# Piirikaavio.net
KiCad netlist of a schematic drawn in Altium Designer
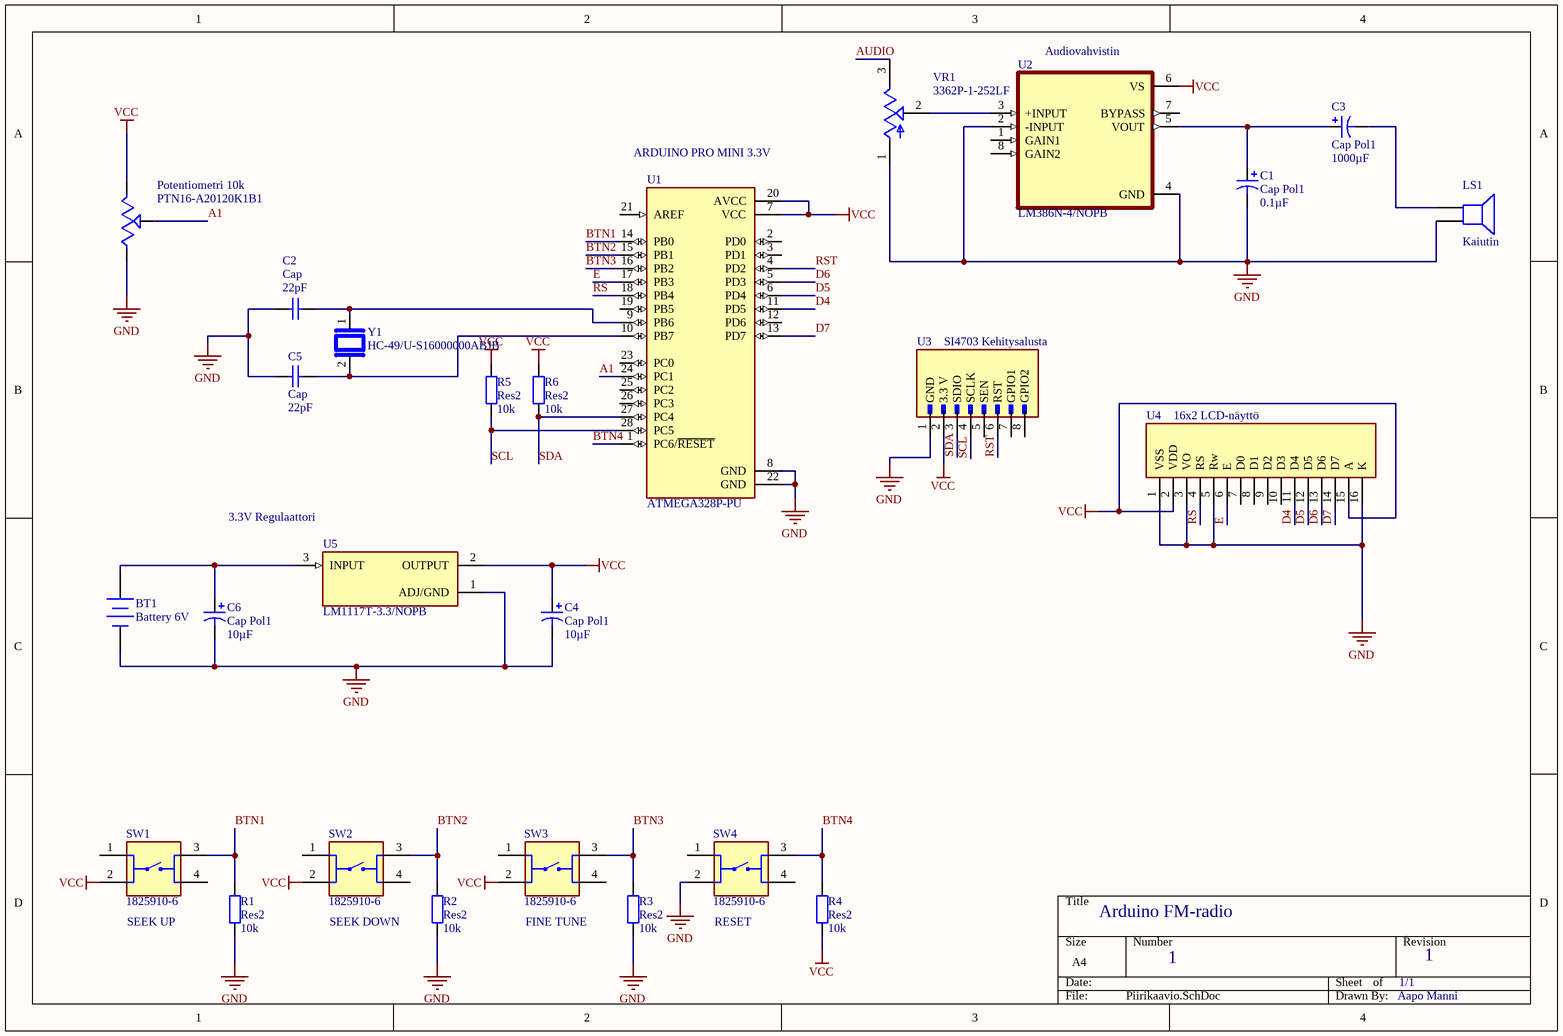
[diagram p0: Piirikaavio.SchDoc]

(export (version "E")
  (design (tool "Eeschema 10.0.6"))
  (components
    (comp (ref "BT1")
      (value "Battery 6V")
      (footprint "BAT-2")
      (description "Multicell Battery")
      (fields (field (name "PUBLISHER") "Altium Limited"))
      (libsource (lib "Miscellaneous Devices") (part "Battery"))
    )
    (comp (ref "C1")
      (value "Cap Pol1")
      (footprint "RB7.6-15")
      (description "Polarized Capacitor (Radial)")
      (fields (field (name "ALTIUM_VALUE") "0.1µF") (field (name "PUBLISHER") "Altium Limited"))
      (libsource (lib "Miscellaneous Devices") (part "Cap Pol1"))
    )
    (comp (ref "C2")
      (value "Cap")
      (footprint "RAD-0.3")
      (description "Capacitor")
      (fields (field (name "ALTIUM_VALUE") "22pF") (field (name "PUBLISHER") "Altium Limited"))
      (libsource (lib "Miscellaneous Devices") (part "Cap"))
    )
    (comp (ref "C3")
      (value "Cap Pol1")
      (footprint "RB7.6-15")
      (description "Polarized Capacitor (Radial)")
      (fields (field (name "ALTIUM_VALUE") "1000µF") (field (name "PUBLISHER") "Altium Limited"))
      (libsource (lib "Miscellaneous Devices") (part "Cap Pol1"))
    )
    (comp (ref "C4")
      (value "Cap Pol1")
      (footprint "RB7.6-15")
      (description "Polarized Capacitor (Radial)")
      (fields (field (name "ALTIUM_VALUE") "10µF") (field (name "PUBLISHER") "Altium Limited"))
      (libsource (lib "Miscellaneous Devices") (part "Cap Pol1"))
    )
    (comp (ref "C5")
      (value "Cap")
      (footprint "RAD-0.3")
      (description "Capacitor")
      (fields (field (name "ALTIUM_VALUE") "22pF") (field (name "PUBLISHER") "Altium Limited"))
      (libsource (lib "Miscellaneous Devices") (part "Cap"))
    )
    (comp (ref "C6")
      (value "Cap Pol1")
      (footprint "RB7.6-15")
      (description "Polarized Capacitor (Radial)")
      (fields (field (name "ALTIUM_VALUE") "10µF") (field (name "PUBLISHER") "Altium Limited"))
      (libsource (lib "Miscellaneous Devices") (part "Cap Pol1"))
    )
    (comp (ref "LS1")
      (value "Kaiutin")
      (footprint "PIN2")
      (description "Loudspeaker")
      (fields (field (name "PUBLISHER") "Altium Limited"))
      (libsource (lib "Miscellaneous Devices") (part "Speaker"))
    )
    (comp (ref "Potentiometri 10k")
      (value "PTN16-A20120K1B1")
      (footprint "POT_PTN16-A20120K1B1")
      (fields (field (name "MF") "CUI Devices"))
      (libsource (lib "PTN16-A20120K1B1") (part "PTN16-A20120K1B1"))
    )
    (comp (ref "R1")
      (value "Res2")
      (footprint "AXIAL-0.4")
      (description "Resistor 10k")
      (fields (field (name "ALTIUM_VALUE") "10k") (field (name "PUBLISHER") "Altium Limited"))
      (libsource (lib "Miscellaneous Devices") (part "Res2"))
    )
    (comp (ref "R2")
      (value "Res2")
      (footprint "AXIAL-0.4")
      (description "Resistor 10k")
      (fields (field (name "ALTIUM_VALUE") "10k") (field (name "PUBLISHER") "Altium Limited"))
      (libsource (lib "Miscellaneous Devices") (part "Res2"))
    )
    (comp (ref "R3")
      (value "Res2")
      (footprint "AXIAL-0.4")
      (description "Resistor 10k")
      (fields (field (name "ALTIUM_VALUE") "10k") (field (name "PUBLISHER") "Altium Limited"))
      (libsource (lib "Miscellaneous Devices") (part "Res2"))
    )
    (comp (ref "R4")
      (value "Res2")
      (footprint "AXIAL-0.4")
      (description "Resistor 10k")
      (fields (field (name "ALTIUM_VALUE") "10k") (field (name "PUBLISHER") "Altium Limited"))
      (libsource (lib "Miscellaneous Devices") (part "Res2"))
    )
    (comp (ref "R5")
      (value "Res2")
      (footprint "AXIAL-0.4")
      (description "Resistor 10k")
      (fields (field (name "ALTIUM_VALUE") "10k") (field (name "PUBLISHER") "Altium Limited"))
      (libsource (lib "Miscellaneous Devices") (part "Res2"))
    )
    (comp (ref "R6")
      (value "Res2")
      (footprint "AXIAL-0.4")
      (description "Resistor 10k")
      (fields (field (name "ALTIUM_VALUE") "10k") (field (name "PUBLISHER") "Altium Limited"))
      (libsource (lib "Miscellaneous Devices") (part "Res2"))
    )
    (comp (ref "SW1")
      (value "1825910-6")
      (footprint "SW_1825910-6-4")
      (description "Switch Push Button OFF (ON) SPST Round Button 0.05A 24VDC Momentary Contact PC Pins Thru-Hole")
      (fields (field (name "MF") "TE Connectivity") (field (name "DIGI-KEY_PART_NUMBER") "450-1650-ND"))
      (libsource (lib "1825910-6") (part "1825910-6"))
    )
    (comp (ref "SW2")
      (value "1825910-6")
      (footprint "SW_1825910-6-4")
      (description "Switch Push Button OFF (ON) SPST Round Button 0.05A 24VDC Momentary Contact PC Pins Thru-Hole")
      (fields (field (name "MF") "TE Connectivity") (field (name "DIGI-KEY_PART_NUMBER") "450-1650-ND"))
      (libsource (lib "1825910-6") (part "1825910-6"))
    )
    (comp (ref "SW3")
      (value "1825910-6")
      (footprint "SW_1825910-6-4")
      (description "Switch Push Button OFF (ON) SPST Round Button 0.05A 24VDC Momentary Contact PC Pins Thru-Hole")
      (fields (field (name "MF") "TE Connectivity") (field (name "DIGI-KEY_PART_NUMBER") "450-1650-ND"))
      (libsource (lib "1825910-6") (part "1825910-6"))
    )
    (comp (ref "SW4")
      (value "1825910-6")
      (footprint "SW_1825910-6-4")
      (description "Switch Push Button OFF (ON) SPST Round Button 0.05A 24VDC Momentary Contact PC Pins Thru-Hole")
      (fields (field (name "MF") "TE Connectivity") (field (name "DIGI-KEY_PART_NUMBER") "450-1650-ND"))
      (libsource (lib "1825910-6") (part "1825910-6"))
    )
    (comp (ref "U1")
      (value "ATMEGA328P-PU")
      (footprint "DIP794W46P254L2967H457Q28B")
      (description "ATmega Series 20 MHz 32 KB Flash 2 KB SRAM 8-Bit Microcontroller - DIP-28")
      (libsource (lib "ATMEGA328P-PU") (part "ATMEGA328P-PU"))
    )
    (comp (ref "U2")
      (value "LM386N-4/NOPB")
      (footprint "DIP794W45P254L959H508Q8")
      (description "LM386 Low Voltage Audio Power Amplifier")
      (libsource (lib "LM386N-4_NOPB") (part "LM386N-4/NOPB"))
    )
    (comp (ref "U3")
      (value "SI4703 Kehitysalusta")
      (footprint "HARWIN_M20-9730846")
      (description "Si4703 Evaluation board")
      (fields (field (name "MF") "Harwin") (field (name "MP") "M20-9730846"))
      (libsource (lib "M20-9730846") (part "M20-9730846"))
    )
    (comp (ref "U4")
      (value "16x2 LCD-näyttö")
      (footprint "TE_6-146276-6")
      (description "16x2 Character LCD Module")
      (fields (field (name "MF") "TE Connectivity") (field (name "MP") "6-146276-6"))
      (libsource (lib "6-146276-6") (part "6-146276-6"))
    )
    (comp (ref "U5")
      (value "LM1117T-3.3/NOPB")
      (footprint "TO254P1054X470X1955-3")
      (description "800-mA 15-V linear voltage regulator")
      (fields (field (name "MF") "Texas Instruments"))
      (libsource (lib "LM1117T-3.3_NOPB") (part "LM1117T-3.3/NOPB"))
    )
    (comp (ref "VR1")
      (value "3362P-1-252LF")
      (footprint "TRIM_3362P-1-252LF")
      (description "10 kOhms Pins Through Hole Trimmer Potentiometer Cermet 1 Turn Top Adjustment")
      (fields (field (name "MF") "Bourns"))
      (libsource (lib "3362P-1-252LF") (part "3362P-1-252LF"))
    )
    (comp (ref "Y1")
      (value "HC-49/U-S16000000ABJB")
      (footprint "XTAL_HC49P488W43L1150T466H350")
      (description "8 MHz Crystal  / HC-49/US")
      (fields (field (name "MF") "Citizen Finedevice"))
      (libsource (lib "HC-49_U-S16000000ABJB") (part "HC-49/U-S16000000ABJB"))
    )
  )
  (nets
    (net (code "1") (name "/A1") (class "Default")
      (node (ref "Potentiometri 10k") (pin "2") (pinfunction "2_2") (pintype "passive"))
      (node (ref "U1") (pin "24") (pinfunction "PC1_24") (pintype "bidirectional"))
    )
    (net (code "2") (name "/AUDIO") (class "Default")
      (node (ref "VR1") (pin "3") (pinfunction "CW_3") (pintype "passive"))
    )
    (net (code "3") (name "/BTN1") (class "Default")
      (node (ref "R1") (pin "1") (pinfunction "1_1") (pintype "passive"))
      (node (ref "SW1") (pin "3") (pinfunction "3_3") (pintype "passive"))
      (node (ref "U1") (pin "14") (pinfunction "PB0_14") (pintype "bidirectional"))
    )
    (net (code "4") (name "/BTN2") (class "Default")
      (node (ref "R2") (pin "1") (pinfunction "1_1") (pintype "passive"))
      (node (ref "SW2") (pin "3") (pinfunction "3_3") (pintype "passive"))
      (node (ref "U1") (pin "15") (pinfunction "PB1_15") (pintype "bidirectional"))
    )
    (net (code "5") (name "/BTN3") (class "Default")
      (node (ref "R3") (pin "1") (pinfunction "1_1") (pintype "passive"))
      (node (ref "SW3") (pin "3") (pinfunction "3_3") (pintype "passive"))
      (node (ref "U1") (pin "16") (pinfunction "PB2_16") (pintype "bidirectional"))
    )
    (net (code "6") (name "/BTN4") (class "Default")
      (node (ref "R4") (pin "1") (pinfunction "1_1") (pintype "passive"))
      (node (ref "SW4") (pin "3") (pinfunction "3_3") (pintype "passive"))
      (node (ref "U1") (pin "1") (pinfunction "PC6/~{RESET}_1") (pintype "bidirectional"))
    )
    (net (code "7") (name "/D4") (class "Default")
      (node (ref "U1") (pin "11") (pinfunction "PD5_11") (pintype "bidirectional"))
      (node (ref "U4") (pin "11") (pinfunction "D4_11") (pintype "passive"))
    )
    (net (code "8") (name "/D5") (class "Default")
      (node (ref "U1") (pin "6") (pinfunction "PD4_6") (pintype "bidirectional"))
      (node (ref "U4") (pin "12") (pinfunction "D5_12") (pintype "passive"))
    )
    (net (code "9") (name "/D6") (class "Default")
      (node (ref "U1") (pin "5") (pinfunction "PD3_5") (pintype "bidirectional"))
      (node (ref "U4") (pin "13") (pinfunction "D6_13") (pintype "passive"))
    )
    (net (code "10") (name "/D7") (class "Default")
      (node (ref "U1") (pin "13") (pinfunction "PD7_13") (pintype "bidirectional"))
      (node (ref "U4") (pin "14") (pinfunction "D7_14") (pintype "passive"))
    )
    (net (code "11") (name "/E") (class "Default")
      (node (ref "U1") (pin "17") (pinfunction "PB3_17") (pintype "bidirectional"))
      (node (ref "U4") (pin "6") (pinfunction "E_6") (pintype "passive"))
    )
    (net (code "12") (name "/RS") (class "Default")
      (node (ref "U1") (pin "18") (pinfunction "PB4_18") (pintype "bidirectional"))
      (node (ref "U4") (pin "4") (pinfunction "RS_4") (pintype "passive"))
    )
    (net (code "13") (name "/RST") (class "Default")
      (node (ref "U1") (pin "4") (pinfunction "PD2_4") (pintype "bidirectional"))
      (node (ref "U3") (pin "6") (pinfunction "RST_6") (pintype "passive"))
    )
    (net (code "14") (name "/SCL") (class "Default")
      (node (ref "R5") (pin "2") (pinfunction "2_2") (pintype "passive"))
      (node (ref "U1") (pin "28") (pinfunction "PC5_28") (pintype "bidirectional"))
      (node (ref "U3") (pin "4") (pinfunction "SCLK_4") (pintype "passive"))
    )
    (net (code "15") (name "/SDA") (class "Default")
      (node (ref "R6") (pin "2") (pinfunction "2_2") (pintype "passive"))
      (node (ref "U1") (pin "27") (pinfunction "PC4_27") (pintype "bidirectional"))
      (node (ref "U3") (pin "3") (pinfunction "SDIO_3") (pintype "passive"))
    )
    (net (code "16") (name "GND") (class "Default")
      (node (ref "BT1") (pin "2") (pinfunction "-_2") (pintype "passive"))
      (node (ref "C1") (pin "2") (pinfunction "2_2") (pintype "passive"))
      (node (ref "C2") (pin "1") (pinfunction "1_1") (pintype "passive"))
      (node (ref "C4") (pin "2") (pinfunction "2_2") (pintype "passive"))
      (node (ref "C5") (pin "1") (pinfunction "1_1") (pintype "passive"))
      (node (ref "C6") (pin "2") (pinfunction "2_2") (pintype "passive"))
      (node (ref "LS1") (pin "2") (pinfunction "2_2") (pintype "passive"))
      (node (ref "Potentiometri 10k") (pin "1") (pinfunction "1_1") (pintype "passive"))
      (node (ref "R1") (pin "2") (pinfunction "2_2") (pintype "passive"))
      (node (ref "R2") (pin "2") (pinfunction "2_2") (pintype "passive"))
      (node (ref "R3") (pin "2") (pinfunction "2_2") (pintype "passive"))
      (node (ref "SW4") (pin "2") (pinfunction "2_2") (pintype "passive"))
      (node (ref "U1") (pin "22") (pinfunction "GND_22") (pintype "power_in"))
      (node (ref "U1") (pin "8") (pinfunction "GND_8") (pintype "power_in"))
      (node (ref "U2") (pin "2") (pinfunction "-INPUT_2") (pintype "input"))
      (node (ref "U2") (pin "4") (pinfunction "GND_4") (pintype "power_in"))
      (node (ref "U3") (pin "1") (pinfunction "GND_1") (pintype "passive"))
      (node (ref "U4") (pin "1") (pinfunction "VSS_1") (pintype "passive"))
      (node (ref "U4") (pin "16") (pinfunction "K_16") (pintype "passive"))
      (node (ref "U4") (pin "3") (pinfunction "VO_3") (pintype "passive"))
      (node (ref "U4") (pin "5") (pinfunction "Rw_5") (pintype "passive"))
      (node (ref "U5") (pin "1") (pinfunction "ADJ/GND_1") (pintype "power_in"))
      (node (ref "VR1") (pin "1") (pinfunction "CCW_1") (pintype "passive"))
    )
    (net (code "17") (name "Net-(BT1-+)") (class "Default")
      (node (ref "BT1") (pin "1") (pinfunction "+_1") (pintype "passive"))
      (node (ref "C6") (pin "1") (pinfunction "1_1") (pintype "passive"))
      (node (ref "U5") (pin "3") (pinfunction "INPUT_3") (pintype "input"))
    )
    (net (code "18") (name "Net-(C3-Pad2)") (class "Default")
      (node (ref "C3") (pin "2") (pinfunction "2_2") (pintype "passive"))
      (node (ref "LS1") (pin "1") (pinfunction "1_1") (pintype "passive"))
    )
    (net (code "19") (name "Net-(U1-PB6)") (class "Default")
      (node (ref "C2") (pin "2") (pinfunction "2_2") (pintype "passive"))
      (node (ref "U1") (pin "9") (pinfunction "PB6_9") (pintype "bidirectional"))
      (node (ref "Y1") (pin "1") (pinfunction "1_1") (pintype "passive"))
    )
    (net (code "20") (name "Net-(U1-PB7)") (class "Default")
      (node (ref "C5") (pin "2") (pinfunction "2_2") (pintype "passive"))
      (node (ref "U1") (pin "10") (pinfunction "PB7_10") (pintype "bidirectional"))
      (node (ref "Y1") (pin "2") (pinfunction "2_2") (pintype "passive"))
    )
    (net (code "21") (name "Net-(U2-+INPUT)") (class "Default")
      (node (ref "U2") (pin "3") (pinfunction "+INPUT_3") (pintype "input"))
      (node (ref "VR1") (pin "2") (pinfunction "WIPER_2") (pintype "passive"))
    )
    (net (code "22") (name "Net-(U2-VOUT)") (class "Default")
      (node (ref "C1") (pin "1") (pinfunction "1_1") (pintype "passive"))
      (node (ref "C3") (pin "1") (pinfunction "1_1") (pintype "passive"))
      (node (ref "U2") (pin "5") (pinfunction "VOUT_5") (pintype "output"))
    )
    (net (code "23") (name "VCC") (class "Default")
      (node (ref "C4") (pin "1") (pinfunction "1_1") (pintype "passive"))
      (node (ref "Potentiometri 10k") (pin "3") (pinfunction "3_3") (pintype "passive"))
      (node (ref "R4") (pin "2") (pinfunction "2_2") (pintype "passive"))
      (node (ref "R5") (pin "1") (pinfunction "1_1") (pintype "passive"))
      (node (ref "R6") (pin "1") (pinfunction "1_1") (pintype "passive"))
      (node (ref "SW1") (pin "2") (pinfunction "2_2") (pintype "passive"))
      (node (ref "SW2") (pin "2") (pinfunction "2_2") (pintype "passive"))
      (node (ref "SW3") (pin "2") (pinfunction "2_2") (pintype "passive"))
      (node (ref "U1") (pin "20") (pinfunction "AVCC_20") (pintype "power_in"))
      (node (ref "U1") (pin "7") (pinfunction "VCC_7") (pintype "power_in"))
      (node (ref "U2") (pin "6") (pinfunction "VS_6") (pintype "power_in"))
      (node (ref "U3") (pin "2") (pinfunction "3.3_V_2") (pintype "passive"))
      (node (ref "U4") (pin "15") (pinfunction "A_15") (pintype "passive"))
      (node (ref "U4") (pin "2") (pinfunction "VDD_2") (pintype "passive"))
      (node (ref "U5") (pin "2") (pinfunction "OUTPUT_2") (pintype "power_in"))
    )
    (net (code "24") (name "unconnected-(SW1-Pad1)") (class "Default")
      (node (ref "SW1") (pin "1") (pinfunction "1_1") (pintype "passive"))
    )
    (net (code "25") (name "unconnected-(SW1-Pad4)") (class "Default")
      (node (ref "SW1") (pin "4") (pinfunction "4_4") (pintype "passive"))
    )
    (net (code "26") (name "unconnected-(SW2-Pad1)") (class "Default")
      (node (ref "SW2") (pin "1") (pinfunction "1_1") (pintype "passive"))
    )
    (net (code "27") (name "unconnected-(SW2-Pad4)") (class "Default")
      (node (ref "SW2") (pin "4") (pinfunction "4_4") (pintype "passive"))
    )
    (net (code "28") (name "unconnected-(SW3-Pad1)") (class "Default")
      (node (ref "SW3") (pin "1") (pinfunction "1_1") (pintype "passive"))
    )
    (net (code "29") (name "unconnected-(SW3-Pad4)") (class "Default")
      (node (ref "SW3") (pin "4") (pinfunction "4_4") (pintype "passive"))
    )
    (net (code "30") (name "unconnected-(SW4-Pad1)") (class "Default")
      (node (ref "SW4") (pin "1") (pinfunction "1_1") (pintype "passive"))
    )
    (net (code "31") (name "unconnected-(SW4-Pad4)") (class "Default")
      (node (ref "SW4") (pin "4") (pinfunction "4_4") (pintype "passive"))
    )
    (net (code "32") (name "unconnected-(U1-AREF-Pad21)") (class "Default")
      (node (ref "U1") (pin "21") (pinfunction "AREF_21") (pintype "input"))
    )
    (net (code "33") (name "unconnected-(U1-PB5-Pad19)") (class "Default")
      (node (ref "U1") (pin "19") (pinfunction "PB5_19") (pintype "bidirectional"))
    )
    (net (code "34") (name "unconnected-(U1-PC0-Pad23)") (class "Default")
      (node (ref "U1") (pin "23") (pinfunction "PC0_23") (pintype "bidirectional"))
    )
    (net (code "35") (name "unconnected-(U1-PC2-Pad25)") (class "Default")
      (node (ref "U1") (pin "25") (pinfunction "PC2_25") (pintype "bidirectional"))
    )
    (net (code "36") (name "unconnected-(U1-PC3-Pad26)") (class "Default")
      (node (ref "U1") (pin "26") (pinfunction "PC3_26") (pintype "bidirectional"))
    )
    (net (code "37") (name "unconnected-(U1-PD0-Pad2)") (class "Default")
      (node (ref "U1") (pin "2") (pinfunction "PD0_2") (pintype "bidirectional"))
    )
    (net (code "38") (name "unconnected-(U1-PD1-Pad3)") (class "Default")
      (node (ref "U1") (pin "3") (pinfunction "PD1_3") (pintype "bidirectional"))
    )
    (net (code "39") (name "unconnected-(U1-PD6-Pad12)") (class "Default")
      (node (ref "U1") (pin "12") (pinfunction "PD6_12") (pintype "bidirectional"))
    )
    (net (code "40") (name "unconnected-(U2-BYPASS-Pad7)") (class "Default")
      (node (ref "U2") (pin "7") (pinfunction "BYPASS_7") (pintype "output"))
    )
    (net (code "41") (name "unconnected-(U2-GAIN1-Pad1)") (class "Default")
      (node (ref "U2") (pin "1") (pinfunction "GAIN1_1") (pintype "input"))
    )
    (net (code "42") (name "unconnected-(U2-GAIN2-Pad8)") (class "Default")
      (node (ref "U2") (pin "8") (pinfunction "GAIN2_8") (pintype "input"))
    )
    (net (code "43") (name "unconnected-(U3-GPIO1-Pad7)") (class "Default")
      (node (ref "U3") (pin "7") (pinfunction "GPIO1_7") (pintype "passive"))
    )
    (net (code "44") (name "unconnected-(U3-GPIO2-Pad8)") (class "Default")
      (node (ref "U3") (pin "8") (pinfunction "GPIO2_8") (pintype "passive"))
    )
    (net (code "45") (name "unconnected-(U3-SEN-Pad5)") (class "Default")
      (node (ref "U3") (pin "5") (pinfunction "SEN_5") (pintype "passive"))
    )
    (net (code "46") (name "unconnected-(U4-D0-Pad7)") (class "Default")
      (node (ref "U4") (pin "7") (pinfunction "D0_7") (pintype "passive"))
    )
    (net (code "47") (name "unconnected-(U4-D1-Pad8)") (class "Default")
      (node (ref "U4") (pin "8") (pinfunction "D1_8") (pintype "passive"))
    )
    (net (code "48") (name "unconnected-(U4-D2-Pad9)") (class "Default")
      (node (ref "U4") (pin "9") (pinfunction "D2_9") (pintype "passive"))
    )
    (net (code "49") (name "unconnected-(U4-D3-Pad10)") (class "Default")
      (node (ref "U4") (pin "10") (pinfunction "D3_10") (pintype "passive"))
    )
  )
)
